# 02config.net
KiCad netlist of a schematic drawn in Altium Designer
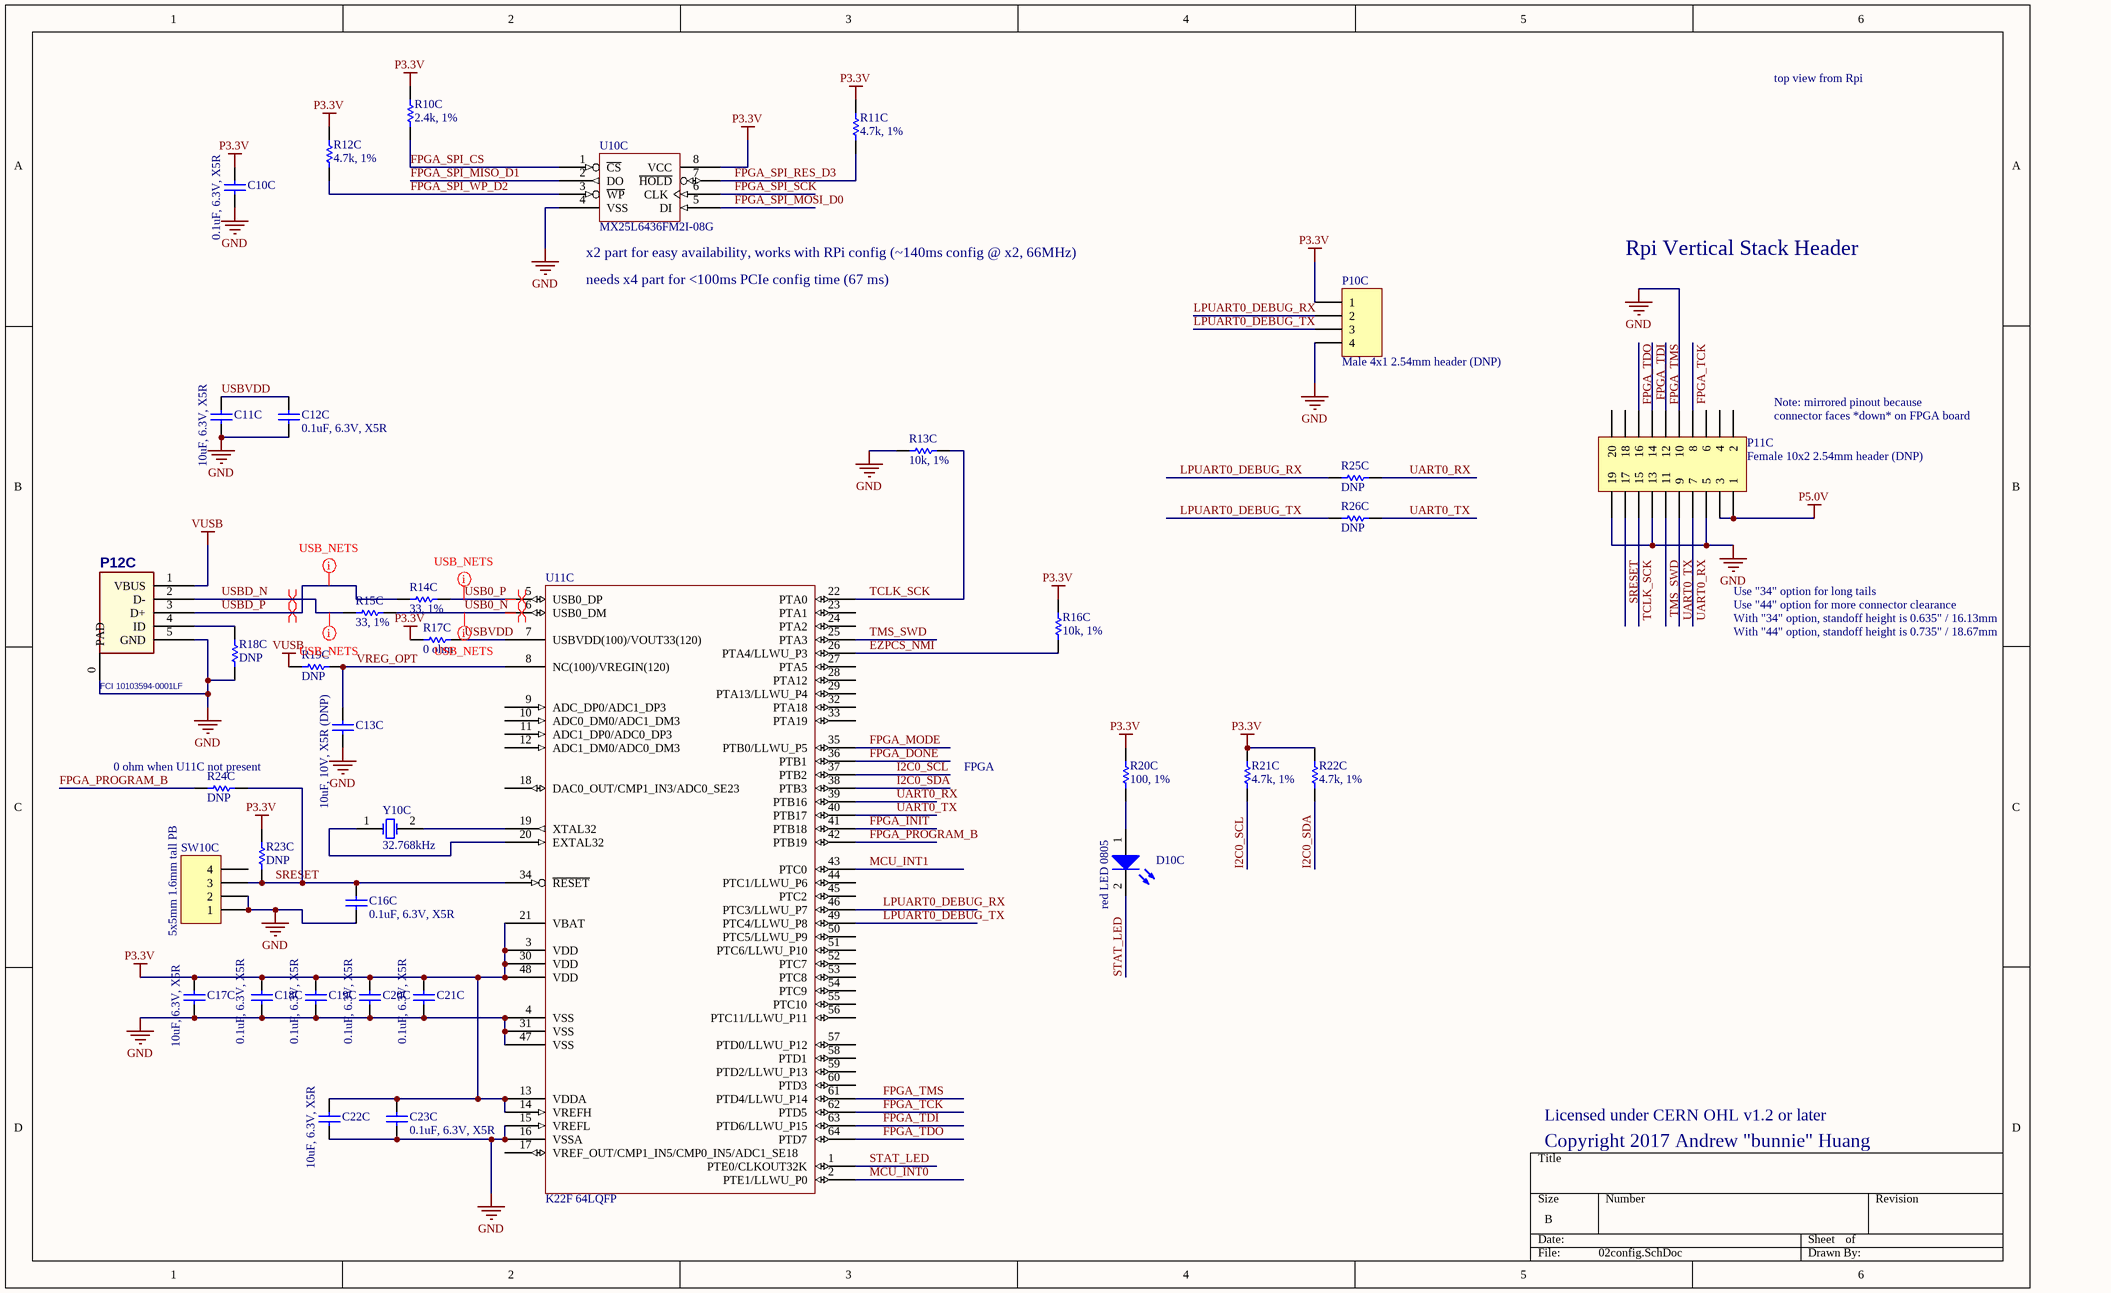
[diagram p0: 02config.SchDoc]

(export (version "E")
  (design (tool "Eeschema 10.0.6"))
  (components
    (comp (ref "C10C")
      (value "0.1uF, 6.3V, X5R")
      (footprint "CAPC0603X03L")
      (description "Capacitor (Semiconductor SIM Model)")
      (fields (field (name "MPN") "CL03A104KQ3NNNC"))
      (libsource (lib "Miscellaneous Devices") (part "Cap Semi"))
    )
    (comp (ref "C11C")
      (value "10uF, 6.3V, X5R")
      (footprint "CAPC1608N")
      (description "Capacitor (Semiconductor SIM Model)")
      (fields (field (name "MPN") "CL10A106MQ8NNNC"))
      (libsource (lib "Miscellaneous Devices") (part "Cap Semi"))
    )
    (comp (ref "C12C")
      (value "0.1uF, 6.3V, X5R")
      (footprint "CAPC0603X03L")
      (description "Capacitor (Semiconductor SIM Model)")
      (fields (field (name "MPN") "CL03A104KQ3NNNC"))
      (libsource (lib "Miscellaneous Devices") (part "Cap Semi"))
    )
    (comp (ref "C13C")
      (value "10uF, 10V, X5R (DNP)")
      (footprint "CAPC2012N")
      (description "Capacitor (Semiconductor SIM Model)")
      (fields (field (name "MPN") "DNP"))
      (libsource (lib "Miscellaneous Devices") (part "Cap Semi"))
    )
    (comp (ref "C16C")
      (value "0.1uF, 6.3V, X5R")
      (footprint "CAPC0603X03L")
      (description "Capacitor (Semiconductor SIM Model)")
      (fields (field (name "MPN") "CL03A104KQ3NNNC"))
      (libsource (lib "Miscellaneous Devices") (part "Cap Semi"))
    )
    (comp (ref "C17C")
      (value "10uF, 6.3V, X5R")
      (footprint "CAPC1608N")
      (description "Capacitor (Semiconductor SIM Model)")
      (fields (field (name "MPN") "CL10A106MQ8NNNC"))
      (libsource (lib "Miscellaneous Devices") (part "Cap Semi"))
    )
    (comp (ref "C18C")
      (value "0.1uF, 6.3V, X5R")
      (footprint "CAPC0603X03L")
      (description "Capacitor (Semiconductor SIM Model)")
      (fields (field (name "MPN") "CL03A104KQ3NNNC"))
      (libsource (lib "Miscellaneous Devices") (part "Cap Semi"))
    )
    (comp (ref "C19C")
      (value "0.1uF, 6.3V, X5R")
      (footprint "CAPC0603X03L")
      (description "Capacitor (Semiconductor SIM Model)")
      (fields (field (name "MPN") "CL03A104KQ3NNNC"))
      (libsource (lib "Miscellaneous Devices") (part "Cap Semi"))
    )
    (comp (ref "C20C")
      (value "0.1uF, 6.3V, X5R")
      (footprint "CAPC0603X03L")
      (description "Capacitor (Semiconductor SIM Model)")
      (fields (field (name "MPN") "CL03A104KQ3NNNC"))
      (libsource (lib "Miscellaneous Devices") (part "Cap Semi"))
    )
    (comp (ref "C21C")
      (value "0.1uF, 6.3V, X5R")
      (footprint "CAPC0603X03L")
      (description "Capacitor (Semiconductor SIM Model)")
      (fields (field (name "MPN") "CL03A104KQ3NNNC"))
      (libsource (lib "Miscellaneous Devices") (part "Cap Semi"))
    )
    (comp (ref "C22C")
      (value "10uF, 6.3V, X5R")
      (footprint "CAPC1608N")
      (description "Capacitor (Semiconductor SIM Model)")
      (fields (field (name "MPN") "CL10A106MQ8NNNC"))
      (libsource (lib "Miscellaneous Devices") (part "Cap Semi"))
    )
    (comp (ref "C23C")
      (value "0.1uF, 6.3V, X5R")
      (footprint "CAPC0603X03L")
      (description "Capacitor (Semiconductor SIM Model)")
      (fields (field (name "MPN") "CL03A104KQ3NNNC"))
      (libsource (lib "Miscellaneous Devices") (part "Cap Semi"))
    )
    (comp (ref "D10C")
      (value "red LED 0805")
      (footprint "CD2012-0805")
      (description "Red LED")
      (fields (field (name "MPN") "CB-2012QRC-P8") (field (name "PUBLISHER") "Altium Limited"))
      (libsource (lib "Miscellaneous Devices") (part "LED2"))
    )
    (comp (ref "P10C")
      (value "Male 4x1 2.54mm header (DNP)")
      (footprint "HDR1X4")
      (description "Header, 4-Pin")
      (fields (field (name "MPN") "DNP") (field (name "PUBLISHER") "Altium Limited"))
      (libsource (lib "Miscellaneous Connectors") (part "Header 4"))
    )
    (comp (ref "P11C")
      (value "Female 10x2 2.54mm header (DNP)")
      (footprint "HDR2X10")
      (description "Header, 10-Pin, Dual row")
      (fields
        (field (name "MPN") "(ESQ/ESW)-110-(34/44/69)-(L/G)-D")
        (field (name "PUBLISHER") "Altium Limited")
      )
      (libsource (lib "Miscellaneous Connectors") (part "Header 10X2"))
    )
    (comp (ref "P12C")
      (value "FCI 10103594-0001LF")
      (footprint "USB_MICRO_B_SMT")
      (description "Micro USB B type connector")
      (fields (field (name "MPN") "10103594-0001LF"))
      (libsource (lib "*") (part "USB_MINI-AB_1"))
    )
    (comp (ref "R10C")
      (value "2.4k, 1%")
      (footprint "CAPC0603X03L")
      (description "Resistor")
      (fields (field (name "MPN") "ANY"))
      (libsource (lib "Miscellaneous Devices") (part "Res1"))
    )
    (comp (ref "R11C")
      (value "4.7k, 1%")
      (footprint "RESC1005N")
      (description "Resistor")
      (fields (field (name "MPN") "RS02U472FT"))
      (libsource (lib "Miscellaneous Devices") (part "Res1"))
    )
    (comp (ref "R12C")
      (value "4.7k, 1%")
      (footprint "RESC1005N")
      (description "Resistor")
      (fields (field (name "MPN") "RS02U472FT"))
      (libsource (lib "Miscellaneous Devices") (part "Res1"))
    )
    (comp (ref "R13C")
      (value "10k, 1%")
      (footprint "RESC1005N")
      (description "Resistor")
      (fields (field (name "MPN") "RS02U103FT"))
      (libsource (lib "Miscellaneous Devices") (part "Res1"))
    )
    (comp (ref "R14C")
      (value "33, 1%")
      (footprint "RESC1005N")
      (description "Resistor")
      (fields (field (name "MPN") "RS02U330FT"))
      (libsource (lib "Miscellaneous Devices") (part "Res1"))
    )
    (comp (ref "R15C")
      (value "33, 1%")
      (footprint "RESC1005N")
      (description "Resistor")
      (fields (field (name "MPN") "RS02U330FT"))
      (libsource (lib "Miscellaneous Devices") (part "Res1"))
    )
    (comp (ref "R16C")
      (value "10k, 1%")
      (footprint "RESC1005N")
      (description "Resistor")
      (fields (field (name "MPN") "RS02U103FT"))
      (libsource (lib "Miscellaneous Devices") (part "Res1"))
    )
    (comp (ref "R17C")
      (value "0 ohm")
      (footprint "RESC1005N")
      (description "Resistor")
      (fields (field (name "MPN") "ANY"))
      (libsource (lib "Miscellaneous Devices") (part "Res1"))
    )
    (comp (ref "R18C")
      (value "DNP")
      (footprint "RESC1005N")
      (description "Resistor")
      (fields (field (name "MPN") "ANY"))
      (libsource (lib "Miscellaneous Devices") (part "Res1"))
    )
    (comp (ref "R19C")
      (value "DNP")
      (footprint "RESC1005N")
      (description "Resistor")
      (fields (field (name "MPN") "ANY"))
      (libsource (lib "Miscellaneous Devices") (part "Res1"))
    )
    (comp (ref "R20C")
      (value "100, 1%")
      (footprint "RESC1005N")
      (description "Resistor")
      (fields (field (name "MPN") "RS02U101FT"))
      (libsource (lib "Miscellaneous Devices") (part "Res1"))
    )
    (comp (ref "R21C")
      (value "4.7k, 1%")
      (footprint "RESC1005N")
      (description "Resistor")
      (fields (field (name "MPN") "ANY"))
      (libsource (lib "Miscellaneous Devices") (part "Res1"))
    )
    (comp (ref "R22C")
      (value "4.7k, 1%")
      (footprint "RESC1005N")
      (description "Resistor")
      (fields (field (name "MPN") "ANY"))
      (libsource (lib "Miscellaneous Devices") (part "Res1"))
    )
    (comp (ref "R23C")
      (value "DNP")
      (footprint "RESC1005N")
      (description "Resistor")
      (libsource (lib "Miscellaneous Devices") (part "Res1"))
    )
    (comp (ref "R24C")
      (value "DNP")
      (footprint "RESC1005N")
      (description "Resistor")
      (fields (field (name "MPN") "ANY"))
      (libsource (lib "Miscellaneous Devices") (part "Res1"))
    )
    (comp (ref "R25C")
      (value "DNP")
      (footprint "RESC1005N")
      (description "Resistor")
      (fields (field (name "MPN") "ANY"))
      (libsource (lib "Miscellaneous Devices") (part "Res1"))
    )
    (comp (ref "R26C")
      (value "DNP")
      (footprint "RESC1005N")
      (description "Resistor")
      (fields (field (name "MPN") "ANY"))
      (libsource (lib "Miscellaneous Devices") (part "Res1"))
    )
    (comp (ref "SW10C")
      (value "5x5mm 1.6mm tall PB")
      (footprint "SWITCH_TS-1187A")
      (description "Chi Fung TS-1187A")
      (fields (field (name "MPN") "SW-PB-5X5-1.6") (field (name "PUBLISHER") "Altium Limited"))
      (libsource (lib "") (part "Header 4_1"))
    )
    (comp (ref "U10C")
      (value "MX25L6436FM2I-08G")
      (footprint "SOIC127P790X216-8N")
      (description "64Mbit SPI NOR FLASH")
      (libsource (lib "commonsch") (part "EN25P05-50GCP"))
    )
    (comp (ref "U11C")
      (value "K22F 64LQFP")
      (footprint "TSQFP50P1200X1200-64N")
      (description "NXP K22F series 64LQFP device")
      (fields (field (name "MPN") "MK22FN128VLH10") (field (name "MFG") "NXP/FREESCALE"))
      (libsource (lib "commonsch-new") (part "MK22-64LQFP"))
    )
    (comp (ref "Y10C")
      (value "32.768kHz")
      (footprint "ABS07-120")
      (description "3.2 x 1.5mm 32.768 kHz crystal, 6pF CL 70k ESR, 20ppm")
      (fields (field (name "MPN") "SJFC1332K06F20"))
      (libsource (lib "Miscellaneous Devices") (part "XTAL"))
    )
  )
  (nets
    (net (code "1") (name "/EZPCS_NMI") (class "Default")
      (node (ref "R16C") (pin "2") (pinfunction "2_2") (pintype "passive"))
      (node (ref "U11C") (pin "26") (pinfunction "PTA4/LLWU_P3_26") (pintype "bidirectional"))
    )
    (net (code "2") (name "/FPGA_DONE") (class "Default")
      (node (ref "U11C") (pin "36") (pinfunction "PTB1_36") (pintype "bidirectional"))
    )
    (net (code "3") (name "/FPGA_INIT") (class "Default")
      (node (ref "U11C") (pin "41") (pinfunction "PTB18_41") (pintype "bidirectional"))
    )
    (net (code "4") (name "/FPGA_MODE") (class "Default")
      (node (ref "U11C") (pin "35") (pinfunction "PTB0/LLWU_P5_35") (pintype "bidirectional"))
    )
    (net (code "5") (name "/FPGA_PROGRAM_B") (class "Default")
      (node (ref "R24C") (pin "1") (pinfunction "1_1") (pintype "passive"))
      (node (ref "U11C") (pin "42") (pinfunction "PTB19_42") (pintype "bidirectional"))
    )
    (net (code "6") (name "/FPGA_SPI_CS") (class "Default")
      (node (ref "R10C") (pin "2") (pinfunction "2_2") (pintype "passive"))
      (node (ref "U10C") (pin "1") (pinfunction "~{CS}_1") (pintype "input"))
    )
    (net (code "7") (name "/FPGA_SPI_MISO_D1") (class "Default")
      (node (ref "U10C") (pin "2") (pinfunction "DO_2") (pintype "output"))
    )
    (net (code "8") (name "/FPGA_SPI_MOSI_D0") (class "Default")
      (node (ref "U10C") (pin "5") (pinfunction "DI_5") (pintype "input"))
    )
    (net (code "9") (name "/FPGA_SPI_RES_D3") (class "Default")
      (node (ref "R11C") (pin "2") (pinfunction "2_2") (pintype "passive"))
      (node (ref "U10C") (pin "7") (pinfunction "~{HOLD}_7") (pintype "bidirectional"))
    )
    (net (code "10") (name "/FPGA_SPI_SCK") (class "Default")
      (node (ref "U10C") (pin "6") (pinfunction "CLK_6") (pintype "input"))
    )
    (net (code "11") (name "/FPGA_SPI_WP_D2") (class "Default")
      (node (ref "R12C") (pin "2") (pinfunction "2_2") (pintype "passive"))
      (node (ref "U10C") (pin "3") (pinfunction "~{WP}_3") (pintype "input"))
    )
    (net (code "12") (name "/FPGA_TCK") (class "Default")
      (node (ref "P11C") (pin "8") (pinfunction "8_8") (pintype "passive"))
      (node (ref "U11C") (pin "62") (pinfunction "PTD5_62") (pintype "bidirectional"))
    )
    (net (code "13") (name "/FPGA_TDI") (class "Default")
      (node (ref "P11C") (pin "14") (pinfunction "14_14") (pintype "passive"))
      (node (ref "U11C") (pin "63") (pinfunction "PTD6/LLWU_P15_63") (pintype "bidirectional"))
    )
    (net (code "14") (name "/FPGA_TDO") (class "Default")
      (node (ref "P11C") (pin "16") (pinfunction "16_16") (pintype "passive"))
      (node (ref "U11C") (pin "64") (pinfunction "PTD7_64") (pintype "bidirectional"))
    )
    (net (code "15") (name "/FPGA_TMS") (class "Default")
      (node (ref "P11C") (pin "12") (pinfunction "12_12") (pintype "passive"))
      (node (ref "U11C") (pin "61") (pinfunction "PTD4/LLWU_P14_61") (pintype "bidirectional"))
    )
    (net (code "16") (name "/I2C0_SCL") (class "Default")
      (node (ref "R21C") (pin "1") (pinfunction "1_1") (pintype "passive"))
      (node (ref "U11C") (pin "37") (pinfunction "PTB2_37") (pintype "bidirectional"))
    )
    (net (code "17") (name "/I2C0_SDA") (class "Default")
      (node (ref "R22C") (pin "1") (pinfunction "1_1") (pintype "passive"))
      (node (ref "U11C") (pin "38") (pinfunction "PTB3_38") (pintype "bidirectional"))
    )
    (net (code "18") (name "/LPUART0_DEBUG_RX") (class "Default")
      (node (ref "P10C") (pin "2") (pinfunction "2_2") (pintype "passive"))
      (node (ref "R25C") (pin "2") (pinfunction "2_2") (pintype "passive"))
      (node (ref "U11C") (pin "46") (pinfunction "PTC3/LLWU_P7_46") (pintype "bidirectional"))
    )
    (net (code "19") (name "/LPUART0_DEBUG_TX") (class "Default")
      (node (ref "P10C") (pin "3") (pinfunction "3_3") (pintype "passive"))
      (node (ref "R26C") (pin "2") (pinfunction "2_2") (pintype "passive"))
      (node (ref "U11C") (pin "49") (pinfunction "PTC4/LLWU_P8_49") (pintype "bidirectional"))
    )
    (net (code "20") (name "/MCU_INT0") (class "Default")
      (node (ref "U11C") (pin "2") (pinfunction "PTE1/LLWU_P0_2") (pintype "bidirectional"))
    )
    (net (code "21") (name "/MCU_INT1") (class "Default")
      (node (ref "U11C") (pin "43") (pinfunction "PTC0_43") (pintype "bidirectional"))
    )
    (net (code "22") (name "/SRESET") (class "Default")
      (node (ref "C16C") (pin "1") (pinfunction "1_1") (pintype "passive"))
      (node (ref "P11C") (pin "17") (pinfunction "17_17") (pintype "passive"))
      (node (ref "R23C") (pin "2") (pinfunction "2_2") (pintype "passive"))
      (node (ref "R24C") (pin "2") (pinfunction "2_2") (pintype "passive"))
      (node (ref "SW10C") (pin "3") (pinfunction "3_3") (pintype "passive"))
      (node (ref "U11C") (pin "34") (pinfunction "~{RESET}_34") (pintype "input"))
    )
    (net (code "23") (name "/STAT_LED") (class "Default")
      (node (ref "D10C") (pin "2") (pinfunction "K_2") (pintype "passive"))
      (node (ref "U11C") (pin "1") (pinfunction "PTE0/CLKOUT32K_1") (pintype "bidirectional"))
    )
    (net (code "24") (name "/TCLK_SCK") (class "Default")
      (node (ref "P11C") (pin "15") (pinfunction "15_15") (pintype "passive"))
      (node (ref "R13C") (pin "1") (pinfunction "1_1") (pintype "passive"))
      (node (ref "U11C") (pin "22") (pinfunction "PTA0_22") (pintype "bidirectional"))
    )
    (net (code "25") (name "/TMS_SWD") (class "Default")
      (node (ref "P11C") (pin "11") (pinfunction "11_11") (pintype "passive"))
      (node (ref "U11C") (pin "25") (pinfunction "PTA3_25") (pintype "bidirectional"))
    )
    (net (code "26") (name "/UART0_RX") (class "Default")
      (node (ref "P11C") (pin "7") (pinfunction "7_7") (pintype "passive"))
      (node (ref "R25C") (pin "1") (pinfunction "1_1") (pintype "passive"))
      (node (ref "U11C") (pin "39") (pinfunction "PTB16_39") (pintype "bidirectional"))
    )
    (net (code "27") (name "/UART0_TX") (class "Default")
      (node (ref "P11C") (pin "9") (pinfunction "9_9") (pintype "passive"))
      (node (ref "R26C") (pin "1") (pinfunction "1_1") (pintype "passive"))
      (node (ref "U11C") (pin "40") (pinfunction "PTB17_40") (pintype "bidirectional"))
    )
    (net (code "28") (name "/USB0_N") (class "Default")
      (node (ref "R15C") (pin "2") (pinfunction "2_2") (pintype "passive"))
      (node (ref "U11C") (pin "6") (pinfunction "USB0_DM_6") (pintype "bidirectional"))
    )
    (net (code "29") (name "/USB0_P") (class "Default")
      (node (ref "R14C") (pin "2") (pinfunction "2_2") (pintype "passive"))
      (node (ref "U11C") (pin "5") (pinfunction "USB0_DP_5") (pintype "bidirectional"))
    )
    (net (code "30") (name "/USBD_N") (class "Default")
      (node (ref "P12C") (pin "2") (pinfunction "D-_2") (pintype "passive"))
      (node (ref "R15C") (pin "1") (pinfunction "1_1") (pintype "passive"))
    )
    (net (code "31") (name "/USBD_P") (class "Default")
      (node (ref "P12C") (pin "3") (pinfunction "D+_3") (pintype "passive"))
      (node (ref "R14C") (pin "1") (pinfunction "1_1") (pintype "passive"))
    )
    (net (code "32") (name "/USBVDD") (class "Default")
      (node (ref "C11C") (pin "1") (pinfunction "1_1") (pintype "passive"))
      (node (ref "C12C") (pin "1") (pinfunction "1_1") (pintype "passive"))
      (node (ref "R17C") (pin "1") (pinfunction "1_1") (pintype "passive"))
      (node (ref "U11C") (pin "7") (pinfunction "USBVDD(100)/VOUT33(120)_7") (pintype "power_in"))
    )
    (net (code "33") (name "/VREG_OPT") (class "Default")
      (node (ref "C13C") (pin "1") (pinfunction "1_1") (pintype "passive"))
      (node (ref "R19C") (pin "1") (pinfunction "1_1") (pintype "passive"))
      (node (ref "U11C") (pin "8") (pinfunction "NC(100)/VREGIN(120)_8") (pintype "power_in"))
    )
    (net (code "34") (name "GND") (class "Default")
      (node (ref "C10C") (pin "2") (pinfunction "2_2") (pintype "passive"))
      (node (ref "C11C") (pin "2") (pinfunction "2_2") (pintype "passive"))
      (node (ref "C12C") (pin "2") (pinfunction "2_2") (pintype "passive"))
      (node (ref "C13C") (pin "2") (pinfunction "2_2") (pintype "passive"))
      (node (ref "C16C") (pin "2") (pinfunction "2_2") (pintype "passive"))
      (node (ref "C17C") (pin "2") (pinfunction "2_2") (pintype "passive"))
      (node (ref "C18C") (pin "2") (pinfunction "2_2") (pintype "passive"))
      (node (ref "C19C") (pin "2") (pinfunction "2_2") (pintype "passive"))
      (node (ref "C20C") (pin "2") (pinfunction "2_2") (pintype "passive"))
      (node (ref "C21C") (pin "2") (pinfunction "2_2") (pintype "passive"))
      (node (ref "C22C") (pin "2") (pinfunction "2_2") (pintype "passive"))
      (node (ref "C23C") (pin "2") (pinfunction "2_2") (pintype "passive"))
      (node (ref "P10C") (pin "4") (pinfunction "4_4") (pintype "passive"))
      (node (ref "P11C") (pin "10") (pinfunction "10_10") (pintype "passive"))
      (node (ref "P11C") (pin "13") (pinfunction "13_13") (pintype "passive"))
      (node (ref "P11C") (pin "19") (pinfunction "19_19") (pintype "passive"))
      (node (ref "P11C") (pin "5") (pinfunction "5_5") (pintype "passive"))
      (node (ref "P12C") (pin "0") (pinfunction "PAD_0") (pintype "passive"))
      (node (ref "P12C") (pin "5") (pinfunction "GND_5") (pintype "passive"))
      (node (ref "R13C") (pin "2") (pinfunction "2_2") (pintype "passive"))
      (node (ref "R18C") (pin "2") (pinfunction "2_2") (pintype "passive"))
      (node (ref "SW10C") (pin "1") (pinfunction "1_1") (pintype "passive"))
      (node (ref "SW10C") (pin "2") (pinfunction "2_2") (pintype "passive"))
      (node (ref "U10C") (pin "4") (pinfunction "VSS_4") (pintype "power_in"))
      (node (ref "U11C") (pin "15") (pinfunction "VREFL_15") (pintype "input"))
      (node (ref "U11C") (pin "16") (pinfunction "VSSA_16") (pintype "power_in"))
      (node (ref "U11C") (pin "31") (pinfunction "VSS_31") (pintype "power_in"))
      (node (ref "U11C") (pin "4") (pinfunction "VSS_4") (pintype "power_in"))
      (node (ref "U11C") (pin "47") (pinfunction "VSS_47") (pintype "power_in"))
    )
    (net (code "35") (name "Net-(D10C-A)") (class "Default")
      (node (ref "D10C") (pin "1") (pinfunction "A_1") (pintype "passive"))
      (node (ref "R20C") (pin "1") (pinfunction "1_1") (pintype "passive"))
    )
    (net (code "36") (name "Net-(P12C-ID)") (class "Default")
      (node (ref "P12C") (pin "4") (pinfunction "ID_4") (pintype "passive"))
      (node (ref "R18C") (pin "1") (pinfunction "1_1") (pintype "passive"))
    )
    (net (code "37") (name "Net-(U11C-EXTAL32)") (class "Default")
      (node (ref "U11C") (pin "20") (pinfunction "EXTAL32_20") (pintype "input"))
      (node (ref "Y10C") (pin "1") (pinfunction "OSC1_1") (pintype "passive"))
    )
    (net (code "38") (name "Net-(U11C-XTAL32)") (class "Default")
      (node (ref "U11C") (pin "19") (pinfunction "XTAL32_19") (pintype "output"))
      (node (ref "Y10C") (pin "2") (pinfunction "OSC2_2") (pintype "passive"))
    )
    (net (code "39") (name "P3.3V") (class "Default")
      (node (ref "C10C") (pin "1") (pinfunction "1_1") (pintype "passive"))
      (node (ref "C17C") (pin "1") (pinfunction "1_1") (pintype "passive"))
      (node (ref "C18C") (pin "1") (pinfunction "1_1") (pintype "passive"))
      (node (ref "C19C") (pin "1") (pinfunction "1_1") (pintype "passive"))
      (node (ref "C20C") (pin "1") (pinfunction "1_1") (pintype "passive"))
      (node (ref "C21C") (pin "1") (pinfunction "1_1") (pintype "passive"))
      (node (ref "C22C") (pin "1") (pinfunction "1_1") (pintype "passive"))
      (node (ref "C23C") (pin "1") (pinfunction "1_1") (pintype "passive"))
      (node (ref "P10C") (pin "1") (pinfunction "1_1") (pintype "passive"))
      (node (ref "R10C") (pin "1") (pinfunction "1_1") (pintype "passive"))
      (node (ref "R11C") (pin "1") (pinfunction "1_1") (pintype "passive"))
      (node (ref "R12C") (pin "1") (pinfunction "1_1") (pintype "passive"))
      (node (ref "R16C") (pin "1") (pinfunction "1_1") (pintype "passive"))
      (node (ref "R17C") (pin "2") (pinfunction "2_2") (pintype "passive"))
      (node (ref "R20C") (pin "2") (pinfunction "2_2") (pintype "passive"))
      (node (ref "R21C") (pin "2") (pinfunction "2_2") (pintype "passive"))
      (node (ref "R22C") (pin "2") (pinfunction "2_2") (pintype "passive"))
      (node (ref "R23C") (pin "1") (pinfunction "1_1") (pintype "passive"))
      (node (ref "U10C") (pin "8") (pinfunction "VCC_8") (pintype "power_in"))
      (node (ref "U11C") (pin "13") (pinfunction "VDDA_13") (pintype "power_in"))
      (node (ref "U11C") (pin "14") (pinfunction "VREFH_14") (pintype "input"))
      (node (ref "U11C") (pin "21") (pinfunction "VBAT_21") (pintype "power_in"))
      (node (ref "U11C") (pin "3") (pinfunction "VDD_3") (pintype "power_in"))
      (node (ref "U11C") (pin "30") (pinfunction "VDD_30") (pintype "power_in"))
      (node (ref "U11C") (pin "48") (pinfunction "VDD_48") (pintype "power_in"))
    )
    (net (code "40") (name "P5.0V") (class "Default")
      (node (ref "P11C") (pin "1") (pinfunction "1_1") (pintype "passive"))
      (node (ref "P11C") (pin "3") (pinfunction "3_3") (pintype "passive"))
    )
    (net (code "41") (name "VUSB") (class "Default")
      (node (ref "P12C") (pin "1") (pinfunction "VBUS_1") (pintype "passive"))
      (node (ref "R19C") (pin "2") (pinfunction "2_2") (pintype "passive"))
    )
    (net (code "42") (name "unconnected-(P11C-Pad2)") (class "Default")
      (node (ref "P11C") (pin "2") (pinfunction "2_2") (pintype "passive"))
    )
    (net (code "43") (name "unconnected-(P11C-Pad4)") (class "Default")
      (node (ref "P11C") (pin "4") (pinfunction "4_4") (pintype "passive"))
    )
    (net (code "44") (name "unconnected-(P11C-Pad6)") (class "Default")
      (node (ref "P11C") (pin "6") (pinfunction "6_6") (pintype "passive"))
    )
    (net (code "45") (name "unconnected-(P11C-Pad18)") (class "Default")
      (node (ref "P11C") (pin "18") (pinfunction "18_18") (pintype "passive"))
    )
    (net (code "46") (name "unconnected-(P11C-Pad20)") (class "Default")
      (node (ref "P11C") (pin "20") (pinfunction "20_20") (pintype "passive"))
    )
    (net (code "47") (name "unconnected-(SW10C-Pad4)") (class "Default")
      (node (ref "SW10C") (pin "4") (pinfunction "4_4") (pintype "passive"))
    )
    (net (code "48") (name "unconnected-(U11C-ADC0_DM0{slash}ADC1_DM3-Pad10)") (class "Default")
      (node (ref "U11C") (pin "10") (pinfunction "ADC0_DM0/ADC1_DM3_10") (pintype "input"))
    )
    (net (code "49") (name "unconnected-(U11C-ADC1_DM0{slash}ADC0_DM3-Pad12)") (class "Default")
      (node (ref "U11C") (pin "12") (pinfunction "ADC1_DM0/ADC0_DM3_12") (pintype "input"))
    )
    (net (code "50") (name "unconnected-(U11C-ADC1_DP0{slash}ADC0_DP3-Pad11)") (class "Default")
      (node (ref "U11C") (pin "11") (pinfunction "ADC1_DP0/ADC0_DP3_11") (pintype "input"))
    )
    (net (code "51") (name "unconnected-(U11C-ADC_DP0{slash}ADC1_DP3-Pad9)") (class "Default")
      (node (ref "U11C") (pin "9") (pinfunction "ADC_DP0/ADC1_DP3_9") (pintype "input"))
    )
    (net (code "52") (name "unconnected-(U11C-DAC0_OUT{slash}CMP1_IN3{slash}ADC0_SE23-Pad18)") (class "Default")
      (node (ref "U11C") (pin "18") (pinfunction "DAC0_OUT/CMP1_IN3/ADC0_SE23_18") (pintype "bidirectional"))
    )
    (net (code "53") (name "unconnected-(U11C-PTA1-Pad23)") (class "Default")
      (node (ref "U11C") (pin "23") (pinfunction "PTA1_23") (pintype "bidirectional"))
    )
    (net (code "54") (name "unconnected-(U11C-PTA2-Pad24)") (class "Default")
      (node (ref "U11C") (pin "24") (pinfunction "PTA2_24") (pintype "bidirectional"))
    )
    (net (code "55") (name "unconnected-(U11C-PTA5-Pad27)") (class "Default")
      (node (ref "U11C") (pin "27") (pinfunction "PTA5_27") (pintype "bidirectional"))
    )
    (net (code "56") (name "unconnected-(U11C-PTA12-Pad28)") (class "Default")
      (node (ref "U11C") (pin "28") (pinfunction "PTA12_28") (pintype "bidirectional"))
    )
    (net (code "57") (name "unconnected-(U11C-PTA13{slash}LLWU_P4-Pad29)") (class "Default")
      (node (ref "U11C") (pin "29") (pinfunction "PTA13/LLWU_P4_29") (pintype "bidirectional"))
    )
    (net (code "58") (name "unconnected-(U11C-PTA18-Pad32)") (class "Default")
      (node (ref "U11C") (pin "32") (pinfunction "PTA18_32") (pintype "bidirectional"))
    )
    (net (code "59") (name "unconnected-(U11C-PTA19-Pad33)") (class "Default")
      (node (ref "U11C") (pin "33") (pinfunction "PTA19_33") (pintype "bidirectional"))
    )
    (net (code "60") (name "unconnected-(U11C-PTC1{slash}LLWU_P6-Pad44)") (class "Default")
      (node (ref "U11C") (pin "44") (pinfunction "PTC1/LLWU_P6_44") (pintype "bidirectional"))
    )
    (net (code "61") (name "unconnected-(U11C-PTC2-Pad45)") (class "Default")
      (node (ref "U11C") (pin "45") (pinfunction "PTC2_45") (pintype "bidirectional"))
    )
    (net (code "62") (name "unconnected-(U11C-PTC5{slash}LLWU_P9-Pad50)") (class "Default")
      (node (ref "U11C") (pin "50") (pinfunction "PTC5/LLWU_P9_50") (pintype "bidirectional"))
    )
    (net (code "63") (name "unconnected-(U11C-PTC6{slash}LLWU_P10-Pad51)") (class "Default")
      (node (ref "U11C") (pin "51") (pinfunction "PTC6/LLWU_P10_51") (pintype "bidirectional"))
    )
    (net (code "64") (name "unconnected-(U11C-PTC7-Pad52)") (class "Default")
      (node (ref "U11C") (pin "52") (pinfunction "PTC7_52") (pintype "bidirectional"))
    )
    (net (code "65") (name "unconnected-(U11C-PTC8-Pad53)") (class "Default")
      (node (ref "U11C") (pin "53") (pinfunction "PTC8_53") (pintype "bidirectional"))
    )
    (net (code "66") (name "unconnected-(U11C-PTC9-Pad54)") (class "Default")
      (node (ref "U11C") (pin "54") (pinfunction "PTC9_54") (pintype "bidirectional"))
    )
    (net (code "67") (name "unconnected-(U11C-PTC10-Pad55)") (class "Default")
      (node (ref "U11C") (pin "55") (pinfunction "PTC10_55") (pintype "bidirectional"))
    )
    (net (code "68") (name "unconnected-(U11C-PTC11{slash}LLWU_P11-Pad56)") (class "Default")
      (node (ref "U11C") (pin "56") (pinfunction "PTC11/LLWU_P11_56") (pintype "bidirectional"))
    )
    (net (code "69") (name "unconnected-(U11C-PTD0{slash}LLWU_P12-Pad57)") (class "Default")
      (node (ref "U11C") (pin "57") (pinfunction "PTD0/LLWU_P12_57") (pintype "bidirectional"))
    )
    (net (code "70") (name "unconnected-(U11C-PTD1-Pad58)") (class "Default")
      (node (ref "U11C") (pin "58") (pinfunction "PTD1_58") (pintype "bidirectional"))
    )
    (net (code "71") (name "unconnected-(U11C-PTD2{slash}LLWU_P13-Pad59)") (class "Default")
      (node (ref "U11C") (pin "59") (pinfunction "PTD2/LLWU_P13_59") (pintype "bidirectional"))
    )
    (net (code "72") (name "unconnected-(U11C-PTD3-Pad60)") (class "Default")
      (node (ref "U11C") (pin "60") (pinfunction "PTD3_60") (pintype "bidirectional"))
    )
    (net (code "73") (name "unconnected-(U11C-VREF_OUT{slash}CMP1_IN5{slash}CMP0_IN5{slash}ADC1_SE18-Pad17)") (class "Default")
      (node (ref "U11C") (pin "17") (pinfunction "VREF_OUT/CMP1_IN5/CMP0_IN5/ADC1_SE18_17") (pintype "bidirectional"))
    )
  )
)
